# transistores.net
KiCad netlist of a schematic drawn in EAGLE
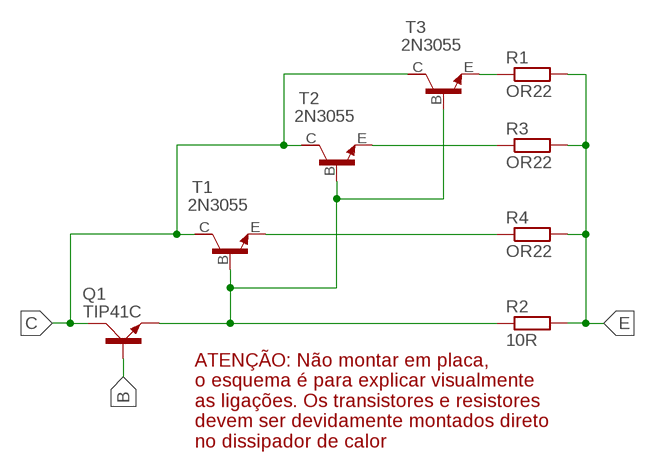
[diagram p0: schematic, sheet 1]

(export (version "E")
  (design (tool "Eeschema 10.0.6"))
  (components
    (comp (ref "Q1")
      (value "TIP41C")
      (footprint "eagle-import:TO220AV")
      (libsource (lib "eagle-import") (part "TIP41C"))
    )
    (comp (ref "R1")
      (value "OR22")
      (footprint "eagle-import:0922_22")
      (libsource (lib "eagle-import") (part "R-EU_0922/22"))
    )
    (comp (ref "R2")
      (value "10R")
      (footprint "eagle-import:0922_22")
      (libsource (lib "eagle-import") (part "R-EU_0922/22"))
    )
    (comp (ref "R3")
      (value "OR22")
      (footprint "eagle-import:0922_22")
      (libsource (lib "eagle-import") (part "R-EU_0922/22"))
    )
    (comp (ref "R4")
      (value "OR22")
      (footprint "eagle-import:0922_22")
      (libsource (lib "eagle-import") (part "R-EU_0922/22"))
    )
    (comp (ref "T1")
      (value "2N3055")
      (footprint "eagle-import:TO3")
      (libsource (lib "eagle-import") (part "2N3055"))
    )
    (comp (ref "T2")
      (value "2N3055")
      (footprint "eagle-import:TO3")
      (libsource (lib "eagle-import") (part "2N3055"))
    )
    (comp (ref "T3")
      (value "2N3055")
      (footprint "eagle-import:TO3")
      (libsource (lib "eagle-import") (part "2N3055"))
    )
  )
  (nets
    (net (code "1") (name "B") (class "Default")
      (node (ref "Q1") (pin "B") (pinfunction "B_B") (pintype "passive"))
    )
    (net (code "2") (name "C") (class "Default")
      (node (ref "Q1") (pin "C") (pinfunction "C_C") (pintype "passive"))
      (node (ref "T1") (pin "C") (pinfunction "C_C") (pintype "passive"))
      (node (ref "T2") (pin "C") (pinfunction "C_C") (pintype "passive"))
      (node (ref "T3") (pin "C") (pinfunction "C_C") (pintype "passive"))
    )
    (net (code "3") (name "E") (class "Default")
      (node (ref "R1") (pin "2") (pinfunction "2_2") (pintype "passive"))
      (node (ref "R2") (pin "2") (pinfunction "2_2") (pintype "passive"))
      (node (ref "R3") (pin "2") (pinfunction "2_2") (pintype "passive"))
      (node (ref "R4") (pin "2") (pinfunction "2_2") (pintype "passive"))
    )
    (net (code "4") (name "Net-(Q1-PadE)") (class "Default")
      (node (ref "Q1") (pin "E") (pinfunction "E_E") (pintype "passive"))
      (node (ref "R2") (pin "1") (pinfunction "1_1") (pintype "passive"))
      (node (ref "T1") (pin "B") (pinfunction "B_B") (pintype "passive"))
      (node (ref "T2") (pin "B") (pinfunction "B_B") (pintype "passive"))
      (node (ref "T3") (pin "B") (pinfunction "B_B") (pintype "passive"))
    )
    (net (code "5") (name "Net-(R1-Pad1)") (class "Default")
      (node (ref "R1") (pin "1") (pinfunction "1_1") (pintype "passive"))
      (node (ref "T3") (pin "E") (pinfunction "E_E") (pintype "passive"))
    )
    (net (code "6") (name "Net-(R3-Pad1)") (class "Default")
      (node (ref "R3") (pin "1") (pinfunction "1_1") (pintype "passive"))
      (node (ref "T2") (pin "E") (pinfunction "E_E") (pintype "passive"))
    )
    (net (code "7") (name "Net-(R4-Pad1)") (class "Default")
      (node (ref "R4") (pin "1") (pinfunction "1_1") (pintype "passive"))
      (node (ref "T1") (pin "E") (pinfunction "E_E") (pintype "passive"))
    )
    (net (code "8") (name "unconnected-(T1-C-PadC{slash})") (class "Default")
      (node (ref "T1") (pin "C/") (pinfunction "C_C/") (pintype "passive"))
    )
    (net (code "9") (name "unconnected-(T2-C-PadC{slash})") (class "Default")
      (node (ref "T2") (pin "C/") (pinfunction "C_C/") (pintype "passive"))
    )
    (net (code "10") (name "unconnected-(T3-C-PadC{slash})") (class "Default")
      (node (ref "T3") (pin "C/") (pinfunction "C_C/") (pintype "passive"))
    )
  )
)
